# carcomputer_split3.net
KiCad netlist of a schematic drawn in EAGLE
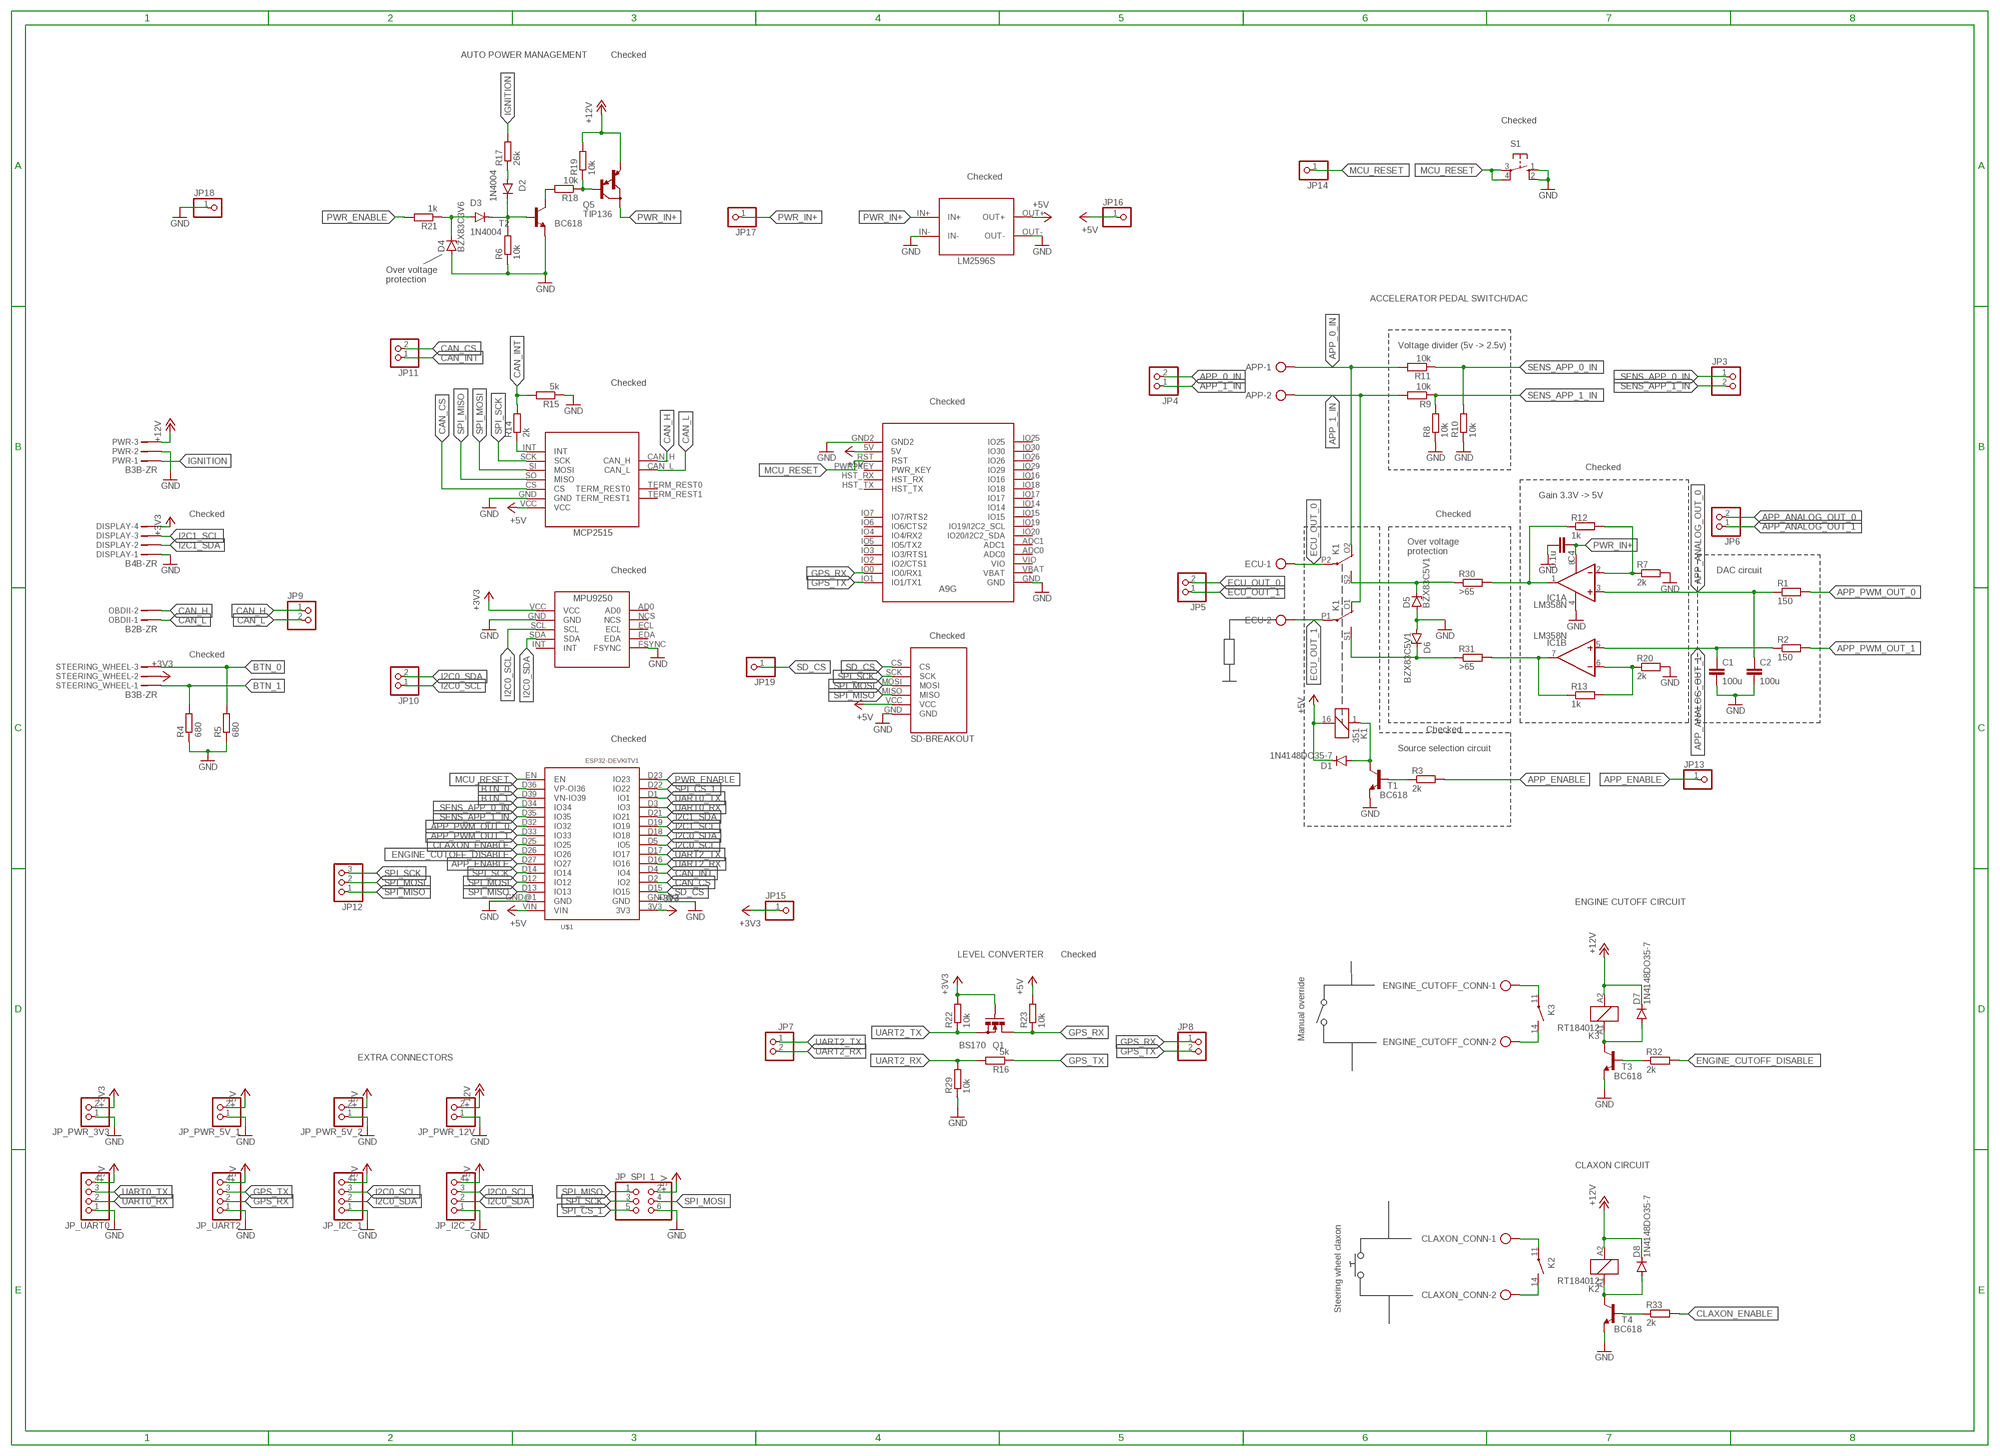
[diagram p0: schematic, sheet 1]

(export (version "E")
  (design (tool "Eeschema 10.0.6"))
  (components
    (comp (ref "APP")
      (value "AK300/2")
      (footprint "eagle-import:AK300_2")
      (libsource (lib "eagle-import") (part "AK300/2"))
    )
    (comp (ref "C1")
      (value "100u")
      (footprint "eagle-import:C025-050X050")
      (libsource (lib "eagle-import") (part "C-EU025-050X050"))
    )
    (comp (ref "C2")
      (value "100u")
      (footprint "eagle-import:C025-050X050")
      (libsource (lib "eagle-import") (part "C-EU025-050X050"))
    )
    (comp (ref "C4")
      (value "0.1u")
      (footprint "eagle-import:C025-050X050")
      (libsource (lib "eagle-import") (part "C-EU025-050X050"))
    )
    (comp (ref "CLAXON_CONN")
      (value "AK300/2")
      (footprint "eagle-import:AK300_2")
      (libsource (lib "eagle-import") (part "AK300/2"))
    )
    (comp (ref "D1")
      (value "1N4148DO35-7")
      (footprint "eagle-import:DO35-7")
      (libsource (lib "eagle-import") (part "1N4148DO35-7"))
    )
    (comp (ref "D2")
      (value "1N4004")
      (footprint "eagle-import:DO41-10")
      (libsource (lib "eagle-import") (part "1N4004"))
    )
    (comp (ref "D3")
      (value "1N4004")
      (footprint "eagle-import:DO41-10")
      (libsource (lib "eagle-import") (part "1N4004"))
    )
    (comp (ref "D4")
      (value "BZX83C3V6")
      (footprint "eagle-import:DO41Z10")
      (libsource (lib "eagle-import") (part "BZX85"))
    )
    (comp (ref "D5")
      (value "BZX83C5V1")
      (footprint "eagle-import:DO41Z10")
      (libsource (lib "eagle-import") (part "BZX85"))
    )
    (comp (ref "D6")
      (value "BZX83C5V1")
      (footprint "eagle-import:DO41Z10")
      (libsource (lib "eagle-import") (part "BZX85"))
    )
    (comp (ref "D7")
      (value "1N4148DO35-7")
      (footprint "eagle-import:DO35-7")
      (libsource (lib "eagle-import") (part "1N4148DO35-7"))
    )
    (comp (ref "D8")
      (value "1N4148DO35-7")
      (footprint "eagle-import:DO35-7")
      (libsource (lib "eagle-import") (part "1N4148DO35-7"))
    )
    (comp (ref "DISPLAY")
      (value "B4B-ZR")
      (footprint "eagle-import:B4B-ZR")
      (fields (field (name "MF") "FARNELL") (field (name "MPN") "B4B-ZR(LF)(SN)"))
      (libsource (lib "eagle-import") (part "?4B-ZRB"))
    )
    (comp (ref "ECU")
      (value "AK300/2")
      (footprint "eagle-import:AK300_2")
      (libsource (lib "eagle-import") (part "AK300/2"))
    )
    (comp (ref "ENGINE_CUTOFF_CONN")
      (value "AK300/2")
      (footprint "eagle-import:AK300_2")
      (libsource (lib "eagle-import") (part "AK300/2"))
    )
    (comp (ref "IC1")
      (value "LM358N")
      (footprint "eagle-import:DIL08")
      (libsource (lib "eagle-import") (part "LM358N"))
    )
    (comp (ref "JP3")
      (value "PINHD-1X2")
      (footprint "eagle-import:1X02")
      (libsource (lib "eagle-import") (part "PINHD-1X2"))
    )
    (comp (ref "JP4")
      (value "PINHD-1X2")
      (footprint "eagle-import:1X02")
      (libsource (lib "eagle-import") (part "PINHD-1X2"))
    )
    (comp (ref "JP5")
      (value "PINHD-1X2")
      (footprint "eagle-import:1X02")
      (libsource (lib "eagle-import") (part "PINHD-1X2"))
    )
    (comp (ref "JP6")
      (value "PINHD-1X2")
      (footprint "eagle-import:1X02")
      (libsource (lib "eagle-import") (part "PINHD-1X2"))
    )
    (comp (ref "JP7")
      (value "PINHD-1X2")
      (footprint "eagle-import:1X02")
      (libsource (lib "eagle-import") (part "PINHD-1X2"))
    )
    (comp (ref "JP8")
      (value "PINHD-1X2")
      (footprint "eagle-import:1X02")
      (libsource (lib "eagle-import") (part "PINHD-1X2"))
    )
    (comp (ref "JP9")
      (value "PINHD-1X2")
      (footprint "eagle-import:1X02")
      (libsource (lib "eagle-import") (part "PINHD-1X2"))
    )
    (comp (ref "JP10")
      (value "PINHD-1X2")
      (footprint "eagle-import:1X02")
      (libsource (lib "eagle-import") (part "PINHD-1X2"))
    )
    (comp (ref "JP11")
      (value "PINHD-1X2")
      (footprint "eagle-import:1X02")
      (libsource (lib "eagle-import") (part "PINHD-1X2"))
    )
    (comp (ref "JP12")
      (value "PINHD-1X3")
      (footprint "eagle-import:1X03")
      (libsource (lib "eagle-import") (part "PINHD-1X3"))
    )
    (comp (ref "JP13")
      (value "PINHD-1X1")
      (footprint "eagle-import:1X01")
      (libsource (lib "eagle-import") (part "PINHD-1X1"))
    )
    (comp (ref "JP14")
      (value "PINHD-1X1")
      (footprint "eagle-import:1X01")
      (libsource (lib "eagle-import") (part "PINHD-1X1"))
    )
    (comp (ref "JP15")
      (value "PINHD-1X1")
      (footprint "eagle-import:1X01")
      (libsource (lib "eagle-import") (part "PINHD-1X1"))
    )
    (comp (ref "JP16")
      (value "PINHD-1X1")
      (footprint "eagle-import:1X01")
      (libsource (lib "eagle-import") (part "PINHD-1X1"))
    )
    (comp (ref "JP17")
      (value "PINHD-1X1")
      (footprint "eagle-import:1X01")
      (libsource (lib "eagle-import") (part "PINHD-1X1"))
    )
    (comp (ref "JP18")
      (value "PINHD-1X1")
      (footprint "eagle-import:1X01")
      (libsource (lib "eagle-import") (part "PINHD-1X1"))
    )
    (comp (ref "JP19")
      (value "PINHD-1X1")
      (footprint "eagle-import:1X01")
      (libsource (lib "eagle-import") (part "PINHD-1X1"))
    )
    (comp (ref "JP_I2C_1")
      (value "PINHD-1X4")
      (footprint "eagle-import:1X04")
      (libsource (lib "eagle-import") (part "PINHD-1X4"))
    )
    (comp (ref "JP_I2C_2")
      (value "PINHD-1X4")
      (footprint "eagle-import:1X04")
      (libsource (lib "eagle-import") (part "PINHD-1X4"))
    )
    (comp (ref "JP_PWR_3V3")
      (value "PINHD-1X2")
      (footprint "eagle-import:1X02")
      (libsource (lib "eagle-import") (part "PINHD-1X2"))
    )
    (comp (ref "JP_PWR_5V_1")
      (value "PINHD-1X2")
      (footprint "eagle-import:1X02")
      (libsource (lib "eagle-import") (part "PINHD-1X2"))
    )
    (comp (ref "JP_PWR_5V_2")
      (value "PINHD-1X2")
      (footprint "eagle-import:1X02")
      (libsource (lib "eagle-import") (part "PINHD-1X2"))
    )
    (comp (ref "JP_PWR_12V")
      (value "PINHD-1X2")
      (footprint "eagle-import:1X02")
      (libsource (lib "eagle-import") (part "PINHD-1X2"))
    )
    (comp (ref "JP_SPI_1")
      (value "PINHD-2X3")
      (footprint "eagle-import:2X03")
      (libsource (lib "eagle-import") (part "PINHD-2X3"))
    )
    (comp (ref "JP_UART0")
      (value "PINHD-1X4")
      (footprint "eagle-import:1X04")
      (libsource (lib "eagle-import") (part "PINHD-1X4"))
    )
    (comp (ref "JP_UART2")
      (value "PINHD-1X4")
      (footprint "eagle-import:1X04")
      (libsource (lib "eagle-import") (part "PINHD-1X4"))
    )
    (comp (ref "K1")
      (value "351")
      (footprint "eagle-import:351")
      (libsource (lib "eagle-import") (part "351"))
    )
    (comp (ref "K2")
      (value "RT184012")
      (footprint "eagle-import:RT-N_O12A3.5")
      (fields (field (name "MF") "TYCO ELECTRONICS"))
      (libsource (lib "eagle-import") (part "RT?184012"))
    )
    (comp (ref "K3")
      (value "RT184012")
      (footprint "eagle-import:RT-N_O12A3.5")
      (fields (field (name "MF") "TYCO ELECTRONICS"))
      (libsource (lib "eagle-import") (part "RT?184012"))
    )
    (comp (ref "OBDII")
      (value "B2B-ZR")
      (footprint "eagle-import:B2B-ZR")
      (libsource (lib "eagle-import") (part "?2B-ZRB"))
    )
    (comp (ref "PWR")
      (value "B3B-ZR")
      (footprint "eagle-import:B3B-ZR")
      (libsource (lib "eagle-import") (part "?3B-ZRB"))
    )
    (comp (ref "Q1")
      (value "BS170")
      (footprint "eagle-import:SOT54E")
      (libsource (lib "eagle-import") (part "BS170"))
    )
    (comp (ref "Q5")
      (value "TIP136")
      (footprint "eagle-import:TO220")
      (libsource (lib "eagle-import") (part "TIP136"))
    )
    (comp (ref "R1")
      (value "150")
      (footprint "eagle-import:0207_7")
      (libsource (lib "eagle-import") (part "R-EU_0207/7"))
    )
    (comp (ref "R2")
      (value "150")
      (footprint "eagle-import:0207_7")
      (libsource (lib "eagle-import") (part "R-EU_0207/7"))
    )
    (comp (ref "R3")
      (value "2k")
      (footprint "eagle-import:0207_7")
      (libsource (lib "eagle-import") (part "R-EU_0207/7"))
    )
    (comp (ref "R4")
      (value "680")
      (footprint "eagle-import:0207_7")
      (libsource (lib "eagle-import") (part "R-EU_0207/7"))
    )
    (comp (ref "R5")
      (value "680")
      (footprint "eagle-import:0207_7")
      (libsource (lib "eagle-import") (part "R-EU_0207/7"))
    )
    (comp (ref "R6")
      (value "10k")
      (footprint "eagle-import:0207_7")
      (libsource (lib "eagle-import") (part "R-EU_0207/7"))
    )
    (comp (ref "R7")
      (value "2k")
      (footprint "eagle-import:0207_7")
      (libsource (lib "eagle-import") (part "R-EU_0207/7"))
    )
    (comp (ref "R8")
      (value "10k")
      (footprint "eagle-import:0207_7")
      (libsource (lib "eagle-import") (part "R-EU_0207/7"))
    )
    (comp (ref "R9")
      (value "10k")
      (footprint "eagle-import:0207_7")
      (libsource (lib "eagle-import") (part "R-EU_0207/7"))
    )
    (comp (ref "R10")
      (value "10k")
      (footprint "eagle-import:0207_7")
      (libsource (lib "eagle-import") (part "R-EU_0207/7"))
    )
    (comp (ref "R11")
      (value "10k")
      (footprint "eagle-import:0207_7")
      (libsource (lib "eagle-import") (part "R-EU_0207/7"))
    )
    (comp (ref "R12")
      (value "1k")
      (footprint "eagle-import:0207_7")
      (libsource (lib "eagle-import") (part "R-EU_0207/7"))
    )
    (comp (ref "R13")
      (value "1k")
      (footprint "eagle-import:0207_7")
      (libsource (lib "eagle-import") (part "R-EU_0207/7"))
    )
    (comp (ref "R14")
      (value "2k")
      (footprint "eagle-import:0207_7")
      (libsource (lib "eagle-import") (part "R-EU_0207/7"))
    )
    (comp (ref "R15")
      (value "5k")
      (footprint "eagle-import:0207_7")
      (libsource (lib "eagle-import") (part "R-EU_0207/7"))
    )
    (comp (ref "R16")
      (value "5k")
      (footprint "eagle-import:0207_7")
      (libsource (lib "eagle-import") (part "R-EU_0207/7"))
    )
    (comp (ref "R17")
      (value "26k")
      (footprint "eagle-import:0207_7")
      (libsource (lib "eagle-import") (part "R-EU_0207/7"))
    )
    (comp (ref "R18")
      (value "10k")
      (footprint "eagle-import:0207_7")
      (libsource (lib "eagle-import") (part "R-EU_0207/7"))
    )
    (comp (ref "R19")
      (value "10k")
      (footprint "eagle-import:0207_7")
      (libsource (lib "eagle-import") (part "R-EU_0207/7"))
    )
    (comp (ref "R20")
      (value "2k")
      (footprint "eagle-import:0207_7")
      (libsource (lib "eagle-import") (part "R-EU_0207/7"))
    )
    (comp (ref "R21")
      (value "1k")
      (footprint "eagle-import:0207_7")
      (libsource (lib "eagle-import") (part "R-EU_0207/7"))
    )
    (comp (ref "R22")
      (value "10k")
      (footprint "eagle-import:0207_7")
      (libsource (lib "eagle-import") (part "R-EU_0207/7"))
    )
    (comp (ref "R23")
      (value "10k")
      (footprint "eagle-import:0207_7")
      (libsource (lib "eagle-import") (part "R-EU_0207/7"))
    )
    (comp (ref "R29")
      (value "10k")
      (footprint "eagle-import:0207_7")
      (libsource (lib "eagle-import") (part "R-EU_0207/7"))
    )
    (comp (ref "R30")
      (value ">65")
      (footprint "eagle-import:0207_7")
      (libsource (lib "eagle-import") (part "R-EU_0207/7"))
    )
    (comp (ref "R31")
      (value ">65")
      (footprint "eagle-import:0207_7")
      (libsource (lib "eagle-import") (part "R-EU_0207/7"))
    )
    (comp (ref "R32")
      (value "2k")
      (footprint "eagle-import:0207_7")
      (libsource (lib "eagle-import") (part "R-EU_0207/7"))
    )
    (comp (ref "R33")
      (value "2k")
      (footprint "eagle-import:0207_7")
      (libsource (lib "eagle-import") (part "R-EU_0207/7"))
    )
    (comp (ref "S1")
      (value "10-XX")
      (footprint "eagle-import:B3F-10XX")
      (fields (field (name "MPN") "B3F-1000"))
      (libsource (lib "eagle-import") (part "10-XX"))
    )
    (comp (ref "STEERING_WHEEL")
      (value "B3B-ZR")
      (footprint "eagle-import:B3B-ZR")
      (libsource (lib "eagle-import") (part "?3B-ZRB"))
    )
    (comp (ref "T1")
      (value "BC618")
      (footprint "eagle-import:TO92-EBC")
      (libsource (lib "eagle-import") (part "BC618"))
    )
    (comp (ref "T2")
      (value "BC618")
      (footprint "eagle-import:TO92-EBC")
      (libsource (lib "eagle-import") (part "BC618"))
    )
    (comp (ref "T3")
      (value "BC618")
      (footprint "eagle-import:TO92-EBC")
      (libsource (lib "eagle-import") (part "BC618"))
    )
    (comp (ref "T4")
      (value "BC618")
      (footprint "eagle-import:TO92-EBC")
      (libsource (lib "eagle-import") (part "BC618"))
    )
    (comp (ref "U$1")
      (value "ESP32DEVKITV1")
      (footprint "eagle-import:ESP32-DEVKITV1")
      (libsource (lib "eagle-import") (part "ESP32DEVKITV1"))
    )
    (comp (ref "U$2")
      (value "MCP2515_DEVBOARDINVERTED")
      (footprint "eagle-import:MCP2515_DEVBOARD_INVERTED")
      (libsource (lib "eagle-import") (part "MCP2515_DEVBOARDINVERTED"))
    )
    (comp (ref "U$3")
      (value "MPU9250_BREAKOUT")
      (footprint "eagle-import:MPU9250_BREAKOUT")
      (libsource (lib "eagle-import") (part "MPU9250_BREAKOUT"))
    )
    (comp (ref "U$4")
      (value "LM2596S")
      (footprint "eagle-import:LM2596S")
      (libsource (lib "eagle-import") (part "LM2596S"))
    )
    (comp (ref "U$5")
      (value "HKD-MICRO-SD-BREAKOUT")
      (footprint "eagle-import:HKD-MICRO-SD-BREAKOUT")
      (libsource (lib "eagle-import") (part "HKD-MICRO-SD-BREAKOUT"))
    )
    (comp (ref "U$6")
      (value "A9G")
      (footprint "eagle-import:A9G")
      (libsource (lib "eagle-import") (part "A9G"))
    )
  )
  (nets
    (net (code "1") (name "+3V3") (class "Default")
      (node (ref "DISPLAY") (pin "4") (pinfunction "1_4") (pintype "passive"))
      (node (ref "JP15") (pin "1") (pinfunction "1_1") (pintype "passive"))
      (node (ref "JP_PWR_3V3") (pin "2") (pinfunction "2_2") (pintype "passive"))
      (node (ref "Q1") (pin "G") (pinfunction "G_G") (pintype "passive"))
      (node (ref "R22") (pin "2") (pinfunction "2_2") (pintype "passive"))
      (node (ref "STEERING_WHEEL") (pin "2") (pinfunction "1_2") (pintype "passive"))
      (node (ref "U$1") (pin "3V3") (pinfunction "3V3_3V3") (pintype "bidirectional"))
      (node (ref "U$3") (pin "VCC") (pinfunction "VCC_VCC") (pintype "bidirectional"))
    )
    (net (code "2") (name "+5V") (class "Default")
      (node (ref "D1") (pin "C") (pinfunction "C_C") (pintype "passive"))
      (node (ref "JP16") (pin "1") (pinfunction "1_1") (pintype "passive"))
      (node (ref "JP_I2C_1") (pin "4") (pinfunction "4_4") (pintype "passive"))
      (node (ref "JP_I2C_2") (pin "4") (pinfunction "4_4") (pintype "passive"))
      (node (ref "JP_PWR_5V_1") (pin "2") (pinfunction "2_2") (pintype "passive"))
      (node (ref "JP_PWR_5V_2") (pin "2") (pinfunction "2_2") (pintype "passive"))
      (node (ref "JP_SPI_1") (pin "2") (pinfunction "2_2") (pintype "passive"))
      (node (ref "JP_UART0") (pin "4") (pinfunction "4_4") (pintype "passive"))
      (node (ref "JP_UART2") (pin "4") (pinfunction "4_4") (pintype "passive"))
      (node (ref "K1") (pin "16") (pinfunction "2_16") (pintype "passive"))
      (node (ref "R23") (pin "2") (pinfunction "2_2") (pintype "passive"))
      (node (ref "U$1") (pin "VIN") (pinfunction "VIN_VIN") (pintype "bidirectional"))
      (node (ref "U$2") (pin "VCC") (pinfunction "VCC_VCC") (pintype "bidirectional"))
      (node (ref "U$4") (pin "OUT+") (pinfunction "OUT+_OUT+") (pintype "bidirectional"))
      (node (ref "U$5") (pin "VCC") (pinfunction "VCC_VCC") (pintype "bidirectional"))
      (node (ref "U$6") (pin "5V") (pinfunction "5V_5V") (pintype "bidirectional"))
    )
    (net (code "3") (name "+12V") (class "Default")
      (node (ref "D7") (pin "C") (pinfunction "C_C") (pintype "passive"))
      (node (ref "D8") (pin "C") (pinfunction "C_C") (pintype "passive"))
      (node (ref "JP_PWR_12V") (pin "2") (pinfunction "2_2") (pintype "passive"))
      (node (ref "K2") (pin "A2") (pinfunction "2_A2") (pintype "passive"))
      (node (ref "K3") (pin "A2") (pinfunction "2_A2") (pintype "passive"))
      (node (ref "PWR") (pin "3") (pinfunction "1_3") (pintype "passive"))
      (node (ref "Q5") (pin "3") (pinfunction "E_3") (pintype "passive"))
      (node (ref "R19") (pin "2") (pinfunction "2_2") (pintype "passive"))
    )
    (net (code "4") (name "APP_0_IN") (class "Default")
      (node (ref "APP") (pin "1") (pinfunction "KL_1") (pintype "passive"))
      (node (ref "JP4") (pin "2") (pinfunction "2_2") (pintype "passive"))
      (node (ref "K1") (pin "O2") (pinfunction "O_O2") (pintype "passive"))
      (node (ref "R11") (pin "2") (pinfunction "2_2") (pintype "passive"))
    )
    (net (code "5") (name "APP_1_IN") (class "Default")
      (node (ref "APP") (pin "2") (pinfunction "KL_2") (pintype "passive"))
      (node (ref "JP4") (pin "1") (pinfunction "1_1") (pintype "passive"))
      (node (ref "K1") (pin "O1") (pinfunction "O_O1") (pintype "passive"))
      (node (ref "R9") (pin "2") (pinfunction "2_2") (pintype "passive"))
    )
    (net (code "6") (name "APP_ANALOG_OUT_0") (class "Default")
      (node (ref "C2") (pin "1") (pinfunction "1_1") (pintype "passive"))
      (node (ref "IC1") (pin "3") (pinfunction "+IN_3") (pintype "input"))
      (node (ref "JP6") (pin "2") (pinfunction "2_2") (pintype "passive"))
      (node (ref "R1") (pin "1") (pinfunction "1_1") (pintype "passive"))
    )
    (net (code "7") (name "APP_ANALOG_OUT_1") (class "Default")
      (node (ref "C1") (pin "1") (pinfunction "1_1") (pintype "passive"))
      (node (ref "IC1") (pin "5") (pinfunction "+IN_5") (pintype "input"))
      (node (ref "JP6") (pin "1") (pinfunction "1_1") (pintype "passive"))
      (node (ref "R2") (pin "1") (pinfunction "1_1") (pintype "passive"))
    )
    (net (code "8") (name "APP_ENABLE") (class "Default")
      (node (ref "JP13") (pin "1") (pinfunction "1_1") (pintype "passive"))
      (node (ref "R3") (pin "2") (pinfunction "2_2") (pintype "passive"))
      (node (ref "U$1") (pin "D27") (pinfunction "IO27_D27") (pintype "bidirectional"))
    )
    (net (code "9") (name "APP_PWM_OUT_0") (class "Default")
      (node (ref "R1") (pin "2") (pinfunction "2_2") (pintype "passive"))
      (node (ref "U$1") (pin "D32") (pinfunction "IO32_D32") (pintype "bidirectional"))
    )
    (net (code "10") (name "APP_PWM_OUT_1") (class "Default")
      (node (ref "R2") (pin "2") (pinfunction "2_2") (pintype "passive"))
      (node (ref "U$1") (pin "D33") (pinfunction "IO33_D33") (pintype "bidirectional"))
    )
    (net (code "11") (name "BTN_0") (class "Default")
      (node (ref "R5") (pin "2") (pinfunction "2_2") (pintype "passive"))
      (node (ref "STEERING_WHEEL") (pin "3") (pinfunction "1_3") (pintype "passive"))
      (node (ref "U$1") (pin "D36") (pinfunction "VP-OI36_D36") (pintype "bidirectional"))
    )
    (net (code "12") (name "BTN_1") (class "Default")
      (node (ref "R4") (pin "2") (pinfunction "2_2") (pintype "passive"))
      (node (ref "STEERING_WHEEL") (pin "1") (pinfunction "1_1") (pintype "passive"))
      (node (ref "U$1") (pin "D39") (pinfunction "VN-IO39_D39") (pintype "bidirectional"))
    )
    (net (code "13") (name "CAN_CS") (class "Default")
      (node (ref "JP11") (pin "2") (pinfunction "2_2") (pintype "passive"))
      (node (ref "U$1") (pin "D2") (pinfunction "IO2_D2") (pintype "bidirectional"))
      (node (ref "U$2") (pin "CS") (pinfunction "CS_CS") (pintype "input"))
    )
    (net (code "14") (name "CAN_H") (class "Default")
      (node (ref "JP9") (pin "1") (pinfunction "1_1") (pintype "passive"))
      (node (ref "OBDII") (pin "2") (pinfunction "1_2") (pintype "passive"))
      (node (ref "U$2") (pin "CAN_H") (pinfunction "CAN_H_CAN_H") (pintype "bidirectional"))
    )
    (net (code "15") (name "CAN_INT") (class "Default")
      (node (ref "JP11") (pin "1") (pinfunction "1_1") (pintype "passive"))
      (node (ref "R14") (pin "2") (pinfunction "2_2") (pintype "passive"))
      (node (ref "R15") (pin "2") (pinfunction "2_2") (pintype "passive"))
      (node (ref "U$1") (pin "D4") (pinfunction "IO4_D4") (pintype "bidirectional"))
    )
    (net (code "16") (name "CAN_L") (class "Default")
      (node (ref "JP9") (pin "2") (pinfunction "2_2") (pintype "passive"))
      (node (ref "OBDII") (pin "1") (pinfunction "1_1") (pintype "passive"))
      (node (ref "U$2") (pin "CAN_L") (pinfunction "CAN_L_CAN_L") (pintype "bidirectional"))
    )
    (net (code "17") (name "CLAXON_ENABLE") (class "Default")
      (node (ref "R33") (pin "2") (pinfunction "2_2") (pintype "passive"))
      (node (ref "U$1") (pin "D25") (pinfunction "IO25_D25") (pintype "bidirectional"))
    )
    (net (code "18") (name "ECU_OUT_0") (class "Default")
      (node (ref "ECU") (pin "1") (pinfunction "KL_1") (pintype "passive"))
      (node (ref "JP5") (pin "2") (pinfunction "2_2") (pintype "passive"))
      (node (ref "K1") (pin "P2") (pinfunction "P_P2") (pintype "passive"))
    )
    (net (code "19") (name "ECU_OUT_1") (class "Default")
      (node (ref "ECU") (pin "2") (pinfunction "KL_2") (pintype "passive"))
      (node (ref "JP5") (pin "1") (pinfunction "1_1") (pintype "passive"))
      (node (ref "K1") (pin "P1") (pinfunction "P_P1") (pintype "passive"))
    )
    (net (code "20") (name "ENGINE_CUTOFF_DISABLE") (class "Default")
      (node (ref "R32") (pin "2") (pinfunction "2_2") (pintype "passive"))
      (node (ref "U$1") (pin "D26") (pinfunction "IO26_D26") (pintype "bidirectional"))
    )
    (net (code "21") (name "GND") (class "Default")
      (node (ref "C1") (pin "2") (pinfunction "2_2") (pintype "passive"))
      (node (ref "C2") (pin "2") (pinfunction "2_2") (pintype "passive"))
      (node (ref "C4") (pin "2") (pinfunction "2_2") (pintype "passive"))
      (node (ref "D4") (pin "A") (pinfunction "A_A") (pintype "passive"))
      (node (ref "D5") (pin "A") (pinfunction "A_A") (pintype "passive"))
      (node (ref "D6") (pin "A") (pinfunction "A_A") (pintype "passive"))
      (node (ref "DISPLAY") (pin "1") (pinfunction "1_1") (pintype "passive"))
      (node (ref "IC1") (pin "4") (pinfunction "V-_4") (pintype "power_in"))
      (node (ref "JP18") (pin "1") (pinfunction "1_1") (pintype "passive"))
      (node (ref "JP_I2C_1") (pin "1") (pinfunction "1_1") (pintype "passive"))
      (node (ref "JP_I2C_2") (pin "1") (pinfunction "1_1") (pintype "passive"))
      (node (ref "JP_PWR_12V") (pin "1") (pinfunction "1_1") (pintype "passive"))
      (node (ref "JP_PWR_3V3") (pin "1") (pinfunction "1_1") (pintype "passive"))
      (node (ref "JP_PWR_5V_1") (pin "1") (pinfunction "1_1") (pintype "passive"))
      (node (ref "JP_PWR_5V_2") (pin "1") (pinfunction "1_1") (pintype "passive"))
      (node (ref "JP_SPI_1") (pin "6") (pinfunction "6_6") (pintype "passive"))
      (node (ref "JP_UART0") (pin "1") (pinfunction "1_1") (pintype "passive"))
      (node (ref "JP_UART2") (pin "1") (pinfunction "1_1") (pintype "passive"))
      (node (ref "PWR") (pin "2") (pinfunction "1_2") (pintype "passive"))
      (node (ref "R10") (pin "1") (pinfunction "1_1") (pintype "passive"))
      (node (ref "R15") (pin "1") (pinfunction "1_1") (pintype "passive"))
      (node (ref "R20") (pin "2") (pinfunction "2_2") (pintype "passive"))
      (node (ref "R29") (pin "1") (pinfunction "1_1") (pintype "passive"))
      (node (ref "R4") (pin "1") (pinfunction "1_1") (pintype "passive"))
      (node (ref "R5") (pin "1") (pinfunction "1_1") (pintype "passive"))
      (node (ref "R6") (pin "1") (pinfunction "1_1") (pintype "passive"))
      (node (ref "R7") (pin "2") (pinfunction "2_2") (pintype "passive"))
      (node (ref "R8") (pin "1") (pinfunction "1_1") (pintype "passive"))
      (node (ref "S1") (pin "1") (pinfunction "S_1") (pintype "passive"))
      (node (ref "S1") (pin "2") (pinfunction "S1_2") (pintype "passive"))
      (node (ref "T1") (pin "E") (pinfunction "E_E") (pintype "passive"))
      (node (ref "T2") (pin "E") (pinfunction "E_E") (pintype "passive"))
      (node (ref "T3") (pin "E") (pinfunction "E_E") (pintype "passive"))
      (node (ref "T4") (pin "E") (pinfunction "E_E") (pintype "passive"))
      (node (ref "U$1") (pin "GND@1") (pinfunction "GND_GND@1") (pintype "bidirectional"))
      (node (ref "U$1") (pin "GND@2") (pinfunction "GND_GND@2") (pintype "bidirectional"))
      (node (ref "U$2") (pin "GND") (pinfunction "GND_GND") (pintype "bidirectional"))
      (node (ref "U$3") (pin "FSYNC") (pinfunction "FSYNC_FSYNC") (pintype "bidirectional"))
      (node (ref "U$3") (pin "GND") (pinfunction "GND_GND") (pintype "bidirectional"))
      (node (ref "U$4") (pin "IN-") (pinfunction "IN-_IN-") (pintype "bidirectional"))
      (node (ref "U$4") (pin "OUT-") (pinfunction "OUT-_OUT-") (pintype "bidirectional"))
      (node (ref "U$5") (pin "GND") (pinfunction "GND_GND") (pintype "bidirectional"))
      (node (ref "U$6") (pin "GND") (pinfunction "GND_GND") (pintype "bidirectional"))
      (node (ref "U$6") (pin "GND2") (pinfunction "GND2_GND2") (pintype "bidirectional"))
    )
    (net (code "22") (name "GPS_RX") (class "Default")
      (node (ref "JP8") (pin "1") (pinfunction "1_1") (pintype "passive"))
      (node (ref "JP_UART2") (pin "2") (pinfunction "2_2") (pintype "passive"))
      (node (ref "Q1") (pin "D") (pinfunction "D_D") (pintype "passive"))
      (node (ref "R23") (pin "1") (pinfunction "1_1") (pintype "passive"))
      (node (ref "U$6") (pin "IO0") (pinfunction "IO0/RX1_IO0") (pintype "bidirectional"))
    )
    (net (code "23") (name "GPS_TX") (class "Default")
      (node (ref "JP8") (pin "2") (pinfunction "2_2") (pintype "passive"))
      (node (ref "JP_UART2") (pin "3") (pinfunction "3_3") (pintype "passive"))
      (node (ref "R16") (pin "1") (pinfunction "1_1") (pintype "passive"))
      (node (ref "U$6") (pin "IO1") (pinfunction "IO1/TX1_IO1") (pintype "bidirectional"))
    )
    (net (code "24") (name "I2C0_SCL") (class "Default")
      (node (ref "JP10") (pin "1") (pinfunction "1_1") (pintype "passive"))
      (node (ref "JP_I2C_1") (pin "3") (pinfunction "3_3") (pintype "passive"))
      (node (ref "JP_I2C_2") (pin "3") (pinfunction "3_3") (pintype "passive"))
      (node (ref "U$1") (pin "D5") (pinfunction "IO5_D5") (pintype "bidirectional"))
      (node (ref "U$3") (pin "SCL") (pinfunction "SCL_SCL") (pintype "bidirectional"))
    )
    (net (code "25") (name "I2C0_SDA") (class "Default")
      (node (ref "JP10") (pin "2") (pinfunction "2_2") (pintype "passive"))
      (node (ref "JP_I2C_1") (pin "2") (pinfunction "2_2") (pintype "passive"))
      (node (ref "JP_I2C_2") (pin "2") (pinfunction "2_2") (pintype "passive"))
      (node (ref "U$1") (pin "D18") (pinfunction "IO18_D18") (pintype "bidirectional"))
      (node (ref "U$3") (pin "SDA") (pinfunction "SDA_SDA") (pintype "bidirectional"))
    )
    (net (code "26") (name "I2C1_SCL") (class "Default")
      (node (ref "DISPLAY") (pin "3") (pinfunction "1_3") (pintype "passive"))
      (node (ref "U$1") (pin "D19") (pinfunction "IO19_D19") (pintype "bidirectional"))
    )
    (net (code "27") (name "I2C1_SDA") (class "Default")
      (node (ref "DISPLAY") (pin "2") (pinfunction "1_2") (pintype "passive"))
      (node (ref "U$1") (pin "D21") (pinfunction "IO21_D21") (pintype "bidirectional"))
    )
    (net (code "28") (name "IGNITION") (class "Default")
      (node (ref "PWR") (pin "1") (pinfunction "1_1") (pintype "passive"))
      (node (ref "R17") (pin "2") (pinfunction "2_2") (pintype "passive"))
    )
    (net (code "29") (name "MCU_RESET") (class "Default")
      (node (ref "JP14") (pin "1") (pinfunction "1_1") (pintype "passive"))
      (node (ref "S1") (pin "3") (pinfunction "P_3") (pintype "passive"))
      (node (ref "S1") (pin "4") (pinfunction "P1_4") (pintype "passive"))
      (node (ref "U$1") (pin "EN") (pinfunction "EN_EN") (pintype "bidirectional"))
      (node (ref "U$6") (pin "RST") (pinfunction "RST_RST") (pintype "bidirectional"))
    )
    (net (code "30") (name "Net-(CLAXON_CONNA-KL)") (class "Default")
      (node (ref "CLAXON_CONN") (pin "1") (pinfunction "KL_1") (pintype "passive"))
      (node (ref "K2") (pin "11") (pinfunction "P_11") (pintype "passive"))
    )
    (net (code "31") (name "Net-(CLAXON_CONNB-KL)") (class "Default")
      (node (ref "CLAXON_CONN") (pin "2") (pinfunction "KL_2") (pintype "passive"))
      (node (ref "K2") (pin "14") (pinfunction "S_14") (pintype "passive"))
    )
    (net (code "32") (name "Net-(D1-PadA)") (class "Default")
      (node (ref "D1") (pin "A") (pinfunction "A_A") (pintype "passive"))
      (node (ref "K1") (pin "1") (pinfunction "1_1") (pintype "passive"))
      (node (ref "T1") (pin "C") (pinfunction "C_C") (pintype "passive"))
    )
    (net (code "33") (name "Net-(D2-PadA)") (class "Default")
      (node (ref "D2") (pin "A") (pinfunction "A_A") (pintype "passive"))
      (node (ref "R17") (pin "1") (pinfunction "1_1") (pintype "passive"))
    )
    (net (code "34") (name "Net-(D2-PadC)") (class "Default")
      (node (ref "D2") (pin "C") (pinfunction "C_C") (pintype "passive"))
      (node (ref "D3") (pin "C") (pinfunction "C_C") (pintype "passive"))
      (node (ref "R6") (pin "2") (pinfunction "2_2") (pintype "passive"))
      (node (ref "T2") (pin "B") (pinfunction "B_B") (pintype "passive"))
    )
    (net (code "35") (name "Net-(D3-PadA)") (class "Default")
      (node (ref "D3") (pin "A") (pinfunction "A_A") (pintype "passive"))
      (node (ref "D4") (pin "C") (pinfunction "C_C") (pintype "passive"))
      (node (ref "R21") (pin "1") (pinfunction "1_1") (pintype "passive"))
    )
    (net (code "36") (name "Net-(ENGINE_CUTOFF_CONNA-KL)") (class "Default")
      (node (ref "ENGINE_CUTOFF_CONN") (pin "1") (pinfunction "KL_1") (pintype "passive"))
      (node (ref "K3") (pin "11") (pinfunction "P_11") (pintype "passive"))
    )
    (net (code "37") (name "Net-(ENGINE_CUTOFF_CONNB-KL)") (class "Default")
      (node (ref "ENGINE_CUTOFF_CONN") (pin "2") (pinfunction "KL_2") (pintype "passive"))
      (node (ref "K3") (pin "14") (pinfunction "S_14") (pintype "passive"))
    )
    (net (code "38") (name "Net-(IC1A--IN)") (class "Default")
      (node (ref "IC1") (pin "2") (pinfunction "-IN_2") (pintype "input"))
      (node (ref "R12") (pin "2") (pinfunction "2_2") (pintype "passive"))
      (node (ref "R7") (pin "1") (pinfunction "1_1") (pintype "passive"))
    )
    (net (code "39") (name "Net-(IC1A-OUT)") (class "Default")
      (node (ref "IC1") (pin "1") (pinfunction "OUT_1") (pintype "output"))
      (node (ref "R12") (pin "1") (pinfunction "1_1") (pintype "passive"))
      (node (ref "R30") (pin "2") (pinfunction "2_2") (pintype "passive"))
    )
    (net (code "40") (name "Net-(IC1B--IN)") (class "Default")
      (node (ref "IC1") (pin "6") (pinfunction "-IN_6") (pintype "input"))
      (node (ref "R13") (pin "2") (pinfunction "2_2") (pintype "passive"))
      (node (ref "R20") (pin "1") (pinfunction "1_1") (pintype "passive"))
    )
    (net (code "41") (name "Net-(IC1B-OUT)") (class "Default")
      (node (ref "IC1") (pin "7") (pinfunction "OUT_7") (pintype "output"))
      (node (ref "R13") (pin "1") (pinfunction "1_1") (pintype "passive"))
      (node (ref "R31") (pin "2") (pinfunction "2_2") (pintype "passive"))
    )
    (net (code "42") (name "Net-(K1B-S)") (class "Default")
      (node (ref "D6") (pin "C") (pinfunction "C_C") (pintype "passive"))
      (node (ref "K1") (pin "S1") (pinfunction "S_S1") (pintype "passive"))
      (node (ref "R31") (pin "1") (pinfunction "1_1") (pintype "passive"))
    )
    (net (code "43") (name "Net-(K1C-S)") (class "Default")
      (node (ref "D5") (pin "C") (pinfunction "C_C") (pintype "passive"))
      (node (ref "K1") (pin "S2") (pinfunction "S_S2") (pintype "passive"))
      (node (ref "R30") (pin "1") (pinfunction "1_1") (pintype "passive"))
    )
    (net (code "44") (name "Net-(K2A-1)") (class "Default")
      (node (ref "D8") (pin "A") (pinfunction "A_A") (pintype "passive"))
      (node (ref "K2") (pin "A1") (pinfunction "1_A1") (pintype "passive"))
      (node (ref "T4") (pin "C") (pinfunction "C_C") (pintype "passive"))
    )
    (net (code "45") (name "Net-(K3A-1)") (class "Default")
      (node (ref "D7") (pin "A") (pinfunction "A_A") (pintype "passive"))
      (node (ref "K3") (pin "A1") (pinfunction "1_A1") (pintype "passive"))
      (node (ref "T3") (pin "C") (pinfunction "C_C") (pintype "passive"))
    )
    (net (code "46") (name "Net-(Q5-B)") (class "Default")
      (node (ref "Q5") (pin "1") (pinfunction "B_1") (pintype "passive"))
      (node (ref "R18") (pin "1") (pinfunction "1_1") (pintype "passive"))
      (node (ref "R19") (pin "1") (pinfunction "1_1") (pintype "passive"))
    )
    (net (code "47") (name "Net-(R3-Pad1)") (class "Default")
      (node (ref "R3") (pin "1") (pinfunction "1_1") (pintype "passive"))
      (node (ref "T1") (pin "B") (pinfunction "B_B") (pintype "passive"))
    )
    (net (code "48") (name "Net-(R14-Pad1)") (class "Default")
      (node (ref "R14") (pin "1") (pinfunction "1_1") (pintype "passive"))
      (node (ref "U$2") (pin "INT") (pinfunction "INT_INT") (pintype "output"))
    )
    (net (code "49") (name "Net-(R18-Pad2)") (class "Default")
      (node (ref "R18") (pin "2") (pinfunction "2_2") (pintype "passive"))
      (node (ref "T2") (pin "C") (pinfunction "C_C") (pintype "passive"))
    )
    (net (code "50") (name "Net-(R32-Pad1)") (class "Default")
      (node (ref "R32") (pin "1") (pinfunction "1_1") (pintype "passive"))
      (node (ref "T3") (pin "B") (pinfunction "B_B") (pintype "passive"))
    )
    (net (code "51") (name "Net-(R33-Pad1)") (class "Default")
      (node (ref "R33") (pin "1") (pinfunction "1_1") (pintype "passive"))
      (node (ref "T4") (pin "B") (pinfunction "B_B") (pintype "passive"))
    )
    (net (code "52") (name "PWR_ENABLE") (class "Default")
      (node (ref "R21") (pin "2") (pinfunction "2_2") (pintype "passive"))
      (node (ref "U$1") (pin "D23") (pinfunction "IO23_D23") (pintype "bidirectional"))
    )
    (net (code "53") (name "PWR_IN+") (class "Default")
      (node (ref "C4") (pin "1") (pinfunction "1_1") (pintype "passive"))
      (node (ref "IC1") (pin "8") (pinfunction "V+_8") (pintype "power_in"))
      (node (ref "JP17") (pin "1") (pinfunction "1_1") (pintype "passive"))
      (node (ref "Q5") (pin "2") (pinfunction "C_2") (pintype "passive"))
      (node (ref "U$4") (pin "IN+") (pinfunction "IN+_IN+") (pintype "bidirectional"))
    )
    (net (code "54") (name "SD_CS") (class "Default")
      (node (ref "JP19") (pin "1") (pinfunction "1_1") (pintype "passive"))
      (node (ref "U$1") (pin "D15") (pinfunction "IO15_D15") (pintype "bidirectional"))
      (node (ref "U$5") (pin "CS") (pinfunction "CS_CS") (pintype "bidirectional"))
    )
    (net (code "55") (name "SENS_APP_0_IN") (class "Default")
      (node (ref "JP3") (pin "1") (pinfunction "1_1") (pintype "passive"))
      (node (ref "R10") (pin "2") (pinfunction "2_2") (pintype "passive"))
      (node (ref "R11") (pin "1") (pinfunction "1_1") (pintype "passive"))
      (node (ref "U$1") (pin "D34") (pinfunction "IO34_D34") (pintype "bidirectional"))
    )
    (net (code "56") (name "SENS_APP_1_IN") (class "Default")
      (node (ref "JP3") (pin "2") (pinfunction "2_2") (pintype "passive"))
      (node (ref "R8") (pin "2") (pinfunction "2_2") (pintype "passive"))
      (node (ref "R9") (pin "1") (pinfunction "1_1") (pintype "passive"))
      (node (ref "U$1") (pin "D35") (pinfunction "IO35_D35") (pintype "bidirectional"))
    )
    (net (code "57") (name "SPI_CS_1") (class "Default")
      (node (ref "JP_SPI_1") (pin "5") (pinfunction "5_5") (pintype "passive"))
      (node (ref "U$1") (pin "D22") (pinfunction "IO22_D22") (pintype "bidirectional"))
    )
    (net (code "58") (name "SPI_MISO") (class "Default")
      (node (ref "JP12") (pin "1") (pinfunction "1_1") (pintype "passive"))
      (node (ref "JP_SPI_1") (pin "1") (pinfunction "1_1") (pintype "passive"))
      (node (ref "U$1") (pin "D13") (pinfunction "IO13_D13") (pintype "bidirectional"))
      (node (ref "U$2") (pin "SO") (pinfunction "MISO_SO") (pintype "output"))
      (node (ref "U$5") (pin "MISO") (pinfunction "MISO_MISO") (pintype "bidirectional"))
    )
    (net (code "59") (name "SPI_MOSI") (class "Default")
      (node (ref "JP12") (pin "2") (pinfunction "2_2") (pintype "passive"))
      (node (ref "JP_SPI_1") (pin "4") (pinfunction "4_4") (pintype "passive"))
      (node (ref "U$1") (pin "D12") (pinfunction "IO12_D12") (pintype "bidirectional"))
      (node (ref "U$2") (pin "SI") (pinfunction "MOSI_SI") (pintype "input"))
      (node (ref "U$5") (pin "MOSI") (pinfunction "MOSI_MOSI") (pintype "bidirectional"))
    )
    (net (code "60") (name "SPI_SCK") (class "Default")
      (node (ref "JP12") (pin "3") (pinfunction "3_3") (pintype "passive"))
      (node (ref "JP_SPI_1") (pin "3") (pinfunction "3_3") (pintype "passive"))
      (node (ref "U$1") (pin "D14") (pinfunction "IO14_D14") (pintype "bidirectional"))
      (node (ref "U$2") (pin "SCK") (pinfunction "SCK_SCK") (pintype "input"))
      (node (ref "U$5") (pin "SCK") (pinfunction "SCK_SCK") (pintype "bidirectional"))
    )
    (net (code "61") (name "UART0_RX") (class "Default")
      (node (ref "JP_UART0") (pin "2") (pinfunction "2_2") (pintype "passive"))
      (node (ref "U$1") (pin "D3") (pinfunction "IO3_D3") (pintype "bidirectional"))
    )
    (net (code "62") (name "UART0_TX") (class "Default")
      (node (ref "JP_UART0") (pin "3") (pinfunction "3_3") (pintype "passive"))
      (node (ref "U$1") (pin "D1") (pinfunction "IO1_D1") (pintype "bidirectional"))
    )
    (net (code "63") (name "UART2_RX") (class "Default")
      (node (ref "JP7") (pin "2") (pinfunction "2_2") (pintype "passive"))
      (node (ref "R16") (pin "2") (pinfunction "2_2") (pintype "passive"))
      (node (ref "R29") (pin "2") (pinfunction "2_2") (pintype "passive"))
      (node (ref "U$1") (pin "D16") (pinfunction "IO16_D16") (pintype "bidirectional"))
    )
    (net (code "64") (name "UART2_TX") (class "Default")
      (node (ref "JP7") (pin "1") (pinfunction "1_1") (pintype "passive"))
      (node (ref "Q1") (pin "S") (pinfunction "S_S") (pintype "passive"))
      (node (ref "R22") (pin "1") (pinfunction "1_1") (pintype "passive"))
      (node (ref "U$1") (pin "D17") (pinfunction "IO17_D17") (pintype "bidirectional"))
    )
    (net (code "65") (name "unconnected-(U$2-PadTERM_REST0)") (class "Default")
      (node (ref "U$2") (pin "TERM_REST0") (pinfunction "TERM_REST0_TERM_REST0") (pintype "bidirectional"))
    )
    (net (code "66") (name "unconnected-(U$2-PadTERM_REST1)") (class "Default")
      (node (ref "U$2") (pin "TERM_REST1") (pinfunction "TERM_REST1_TERM_REST1") (pintype "bidirectional"))
    )
    (net (code "67") (name "unconnected-(U$3-PadAD0)") (class "Default")
      (node (ref "U$3") (pin "AD0") (pinfunction "AD0_AD0") (pintype "bidirectional"))
    )
    (net (code "68") (name "unconnected-(U$3-PadECL)") (class "Default")
      (node (ref "U$3") (pin "ECL") (pinfunction "ECL_ECL") (pintype "bidirectional"))
    )
    (net (code "69") (name "unconnected-(U$3-PadEDA)") (class "Default")
      (node (ref "U$3") (pin "EDA") (pinfunction "EDA_EDA") (pintype "bidirectional"))
    )
    (net (code "70") (name "unconnected-(U$3-PadINT)") (class "Default")
      (node (ref "U$3") (pin "INT") (pinfunction "INT_INT") (pintype "bidirectional"))
    )
    (net (code "71") (name "unconnected-(U$3-PadNCS)") (class "Default")
      (node (ref "U$3") (pin "NCS") (pinfunction "NCS_NCS") (pintype "bidirectional"))
    )
    (net (code "72") (name "unconnected-(U$6-IO2{slash}CTS1-PadIO2)") (class "Default")
      (node (ref "U$6") (pin "IO2") (pinfunction "IO2/CTS1_IO2") (pintype "bidirectional"))
    )
    (net (code "73") (name "unconnected-(U$6-IO3{slash}RTS1-PadIO3)") (class "Default")
      (node (ref "U$6") (pin "IO3") (pinfunction "IO3/RTS1_IO3") (pintype "bidirectional"))
    )
    (net (code "74") (name "unconnected-(U$6-IO4{slash}RX2-PadIO4)") (class "Default")
      (node (ref "U$6") (pin "IO4") (pinfunction "IO4/RX2_IO4") (pintype "bidirectional"))
    )
    (net (code "75") (name "unconnected-(U$6-IO5{slash}TX2-PadIO5)") (class "Default")
      (node (ref "U$6") (pin "IO5") (pinfunction "IO5/TX2_IO5") (pintype "bidirectional"))
    )
    (net (code "76") (name "unconnected-(U$6-IO6{slash}CTS2-PadIO6)") (class "Default")
      (node (ref "U$6") (pin "IO6") (pinfunction "IO6/CTS2_IO6") (pintype "bidirectional"))
    )
    (net (code "77") (name "unconnected-(U$6-IO7{slash}RTS2-PadIO7)") (class "Default")
      (node (ref "U$6") (pin "IO7") (pinfunction "IO7/RTS2_IO7") (pintype "bidirectional"))
    )
    (net (code "78") (name "unconnected-(U$6-IO19{slash}I2C2_SCL-PadIO19)") (class "Default")
      (node (ref "U$6") (pin "IO19") (pinfunction "IO19/I2C2_SCL_IO19") (pintype "bidirectional"))
    )
    (net (code "79") (name "unconnected-(U$6-IO20{slash}I2C2_SDA-PadIO20)") (class "Default")
      (node (ref "U$6") (pin "IO20") (pinfunction "IO20/I2C2_SDA_IO20") (pintype "bidirectional"))
    )
    (net (code "80") (name "unconnected-(U$6-PadADC0)") (class "Default")
      (node (ref "U$6") (pin "ADC0") (pinfunction "ADC0_ADC0") (pintype "bidirectional"))
    )
    (net (code "81") (name "unconnected-(U$6-PadADC1)") (class "Default")
      (node (ref "U$6") (pin "ADC1") (pinfunction "ADC1_ADC1") (pintype "bidirectional"))
    )
    (net (code "82") (name "unconnected-(U$6-PadHST_RX)") (class "Default")
      (node (ref "U$6") (pin "HST_RX") (pinfunction "HST_RX_HST_RX") (pintype "bidirectional"))
    )
    (net (code "83") (name "unconnected-(U$6-PadHST_TX)") (class "Default")
      (node (ref "U$6") (pin "HST_TX") (pinfunction "HST_TX_HST_TX") (pintype "bidirectional"))
    )
    (net (code "84") (name "unconnected-(U$6-PadIO14)") (class "Default")
      (node (ref "U$6") (pin "IO14") (pinfunction "IO14_IO14") (pintype "bidirectional"))
    )
    (net (code "85") (name "unconnected-(U$6-PadIO15)") (class "Default")
      (node (ref "U$6") (pin "IO15") (pinfunction "IO15_IO15") (pintype "bidirectional"))
    )
    (net (code "86") (name "unconnected-(U$6-PadIO16)") (class "Default")
      (node (ref "U$6") (pin "IO16") (pinfunction "IO16_IO16") (pintype "bidirectional"))
    )
    (net (code "87") (name "unconnected-(U$6-PadIO17)") (class "Default")
      (node (ref "U$6") (pin "IO17") (pinfunction "IO17_IO17") (pintype "bidirectional"))
    )
    (net (code "88") (name "unconnected-(U$6-PadIO18)") (class "Default")
      (node (ref "U$6") (pin "IO18") (pinfunction "IO18_IO18") (pintype "bidirectional"))
    )
    (net (code "89") (name "unconnected-(U$6-PadIO25)") (class "Default")
      (node (ref "U$6") (pin "IO25") (pinfunction "IO25_IO25") (pintype "bidirectional"))
    )
    (net (code "90") (name "unconnected-(U$6-PadIO26)") (class "Default")
      (node (ref "U$6") (pin "IO26") (pinfunction "IO26_IO26") (pintype "bidirectional"))
    )
    (net (code "91") (name "unconnected-(U$6-PadIO29)") (class "Default")
      (node (ref "U$6") (pin "IO29") (pinfunction "IO29_IO29") (pintype "bidirectional"))
    )
    (net (code "92") (name "unconnected-(U$6-PadIO30)") (class "Default")
      (node (ref "U$6") (pin "IO30") (pinfunction "IO30_IO30") (pintype "bidirectional"))
    )
    (net (code "93") (name "unconnected-(U$6-PadPWR_KEY)") (class "Default")
      (node (ref "U$6") (pin "PWR_KEY") (pinfunction "PWR_KEY_PWR_KEY") (pintype "bidirectional"))
    )
    (net (code "94") (name "unconnected-(U$6-PadVBAT)") (class "Default")
      (node (ref "U$6") (pin "VBAT") (pinfunction "VBAT_VBAT") (pintype "bidirectional"))
    )
    (net (code "95") (name "unconnected-(U$6-PadVIO)") (class "Default")
      (node (ref "U$6") (pin "VIO") (pinfunction "VIO_VIO") (pintype "bidirectional"))
    )
  )
)
